# Jetson_PCB_SCH.net
KiCad netlist of a schematic drawn in EAGLE
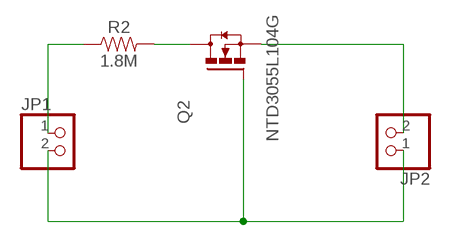
[diagram p0: schematic, sheet 1]

(export (version "E")
  (design (tool "Eeschema 10.0.6"))
  (components
    (comp (ref "JP1")
      (value "PINHD-1X2")
      (footprint "eagle-import:1X02")
      (libsource (lib "eagle-import") (part "PINHD-1X2"))
    )
    (comp (ref "JP2")
      (value "PINHD-1X2")
      (footprint "eagle-import:1X02")
      (libsource (lib "eagle-import") (part "PINHD-1X2"))
    )
    (comp (ref "Q2")
      (value "NTD3055L104G")
      (footprint "eagle-import:DPAK4")
      (fields (field (name "MANUFACTURER") "ON SEMICONDUCTORS") (field (name "CREATED_BY") "PCBLayout.com"))
      (libsource (lib "eagle-import") (part "NTD3055L104G"))
    )
    (comp (ref "R2")
      (value "1.8M")
      (footprint "eagle-import:0603")
      (libsource (lib "eagle-import") (part "1.8MOHM"))
    )
  )
  (nets
    (net (code "1") (name "Net-(JP1-Pad1)") (class "Default")
      (node (ref "JP1") (pin "1") (pinfunction "1_1") (pintype "passive"))
      (node (ref "R2") (pin "1") (pinfunction "1_1") (pintype "passive"))
    )
    (net (code "2") (name "Net-(Q2-D-Pad2)") (class "Default")
      (node (ref "Q2") (pin "2") (pinfunction "D_2") (pintype "passive"))
      (node (ref "Q2") (pin "4") (pinfunction "D_4") (pintype "passive"))
      (node (ref "R2") (pin "2") (pinfunction "2_2") (pintype "passive"))
    )
    (net (code "3") (name "Net-(Q2-G)") (class "Default")
      (node (ref "JP1") (pin "2") (pinfunction "2_2") (pintype "passive"))
      (node (ref "JP2") (pin "1") (pinfunction "1_1") (pintype "passive"))
      (node (ref "Q2") (pin "1") (pinfunction "G_1") (pintype "passive"))
    )
    (net (code "4") (name "Net-(Q2-S)") (class "Default")
      (node (ref "JP2") (pin "2") (pinfunction "2_2") (pintype "passive"))
      (node (ref "Q2") (pin "3") (pinfunction "S_3") (pintype "passive"))
    )
  )
)
